# lightino.net
KiCad netlist of a schematic drawn in EAGLE
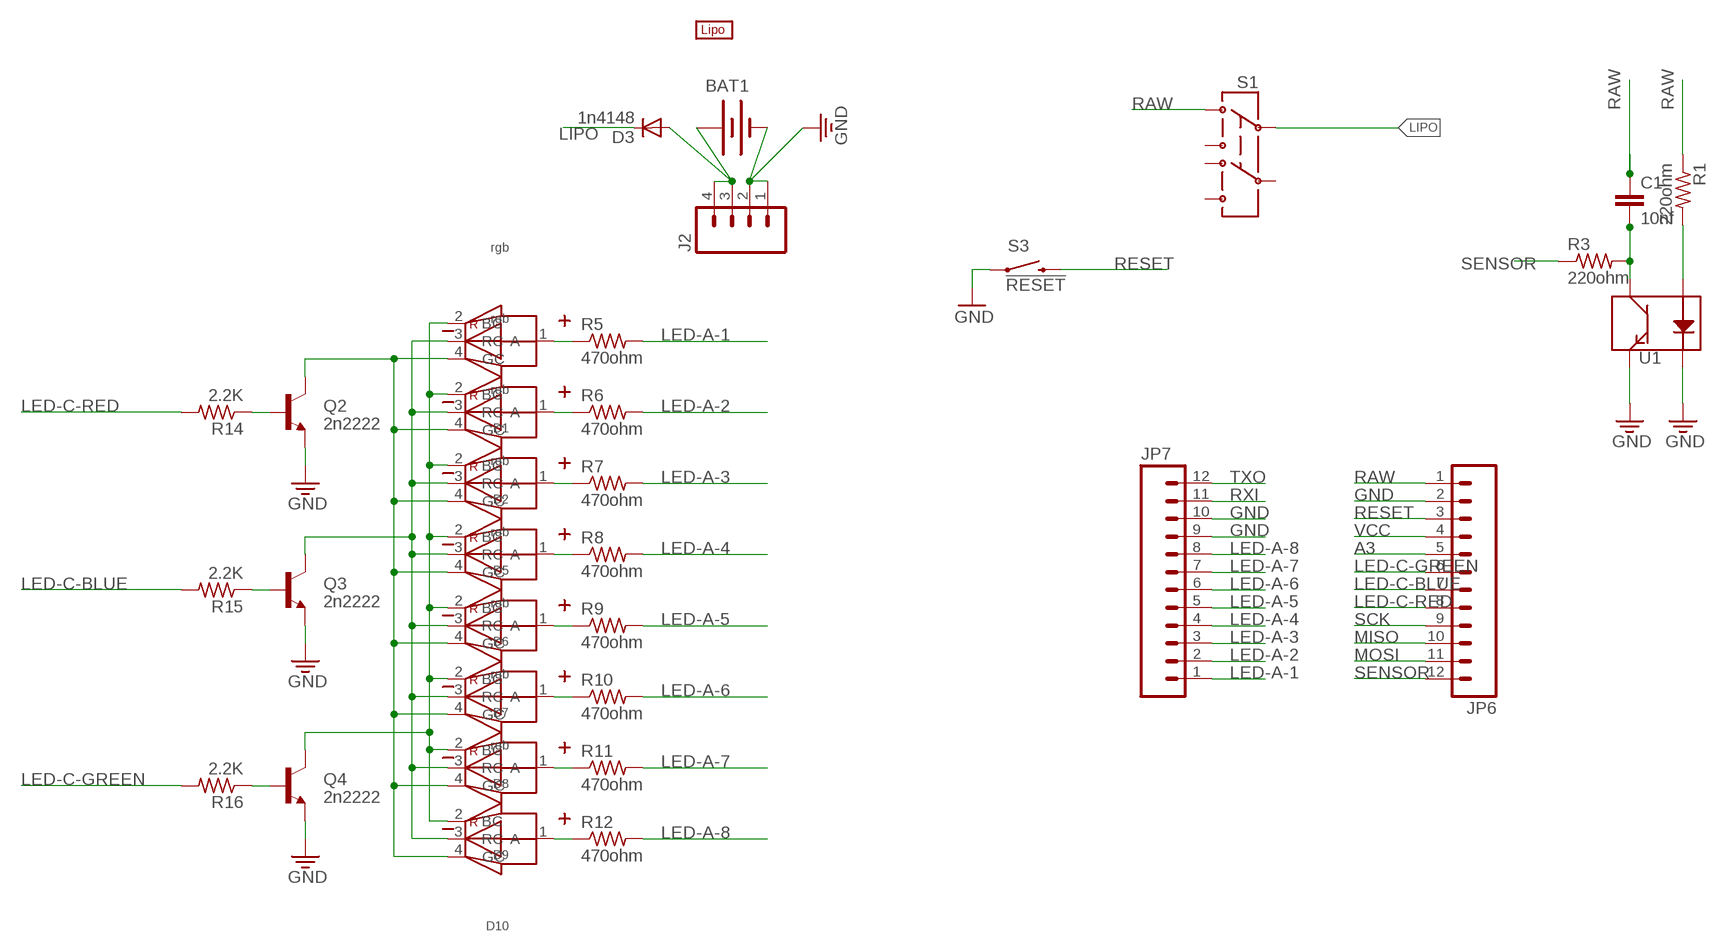
[diagram p0: schematic, sheet 1]

(export (version "E")
  (design (tool "Eeschema 10.0.6"))
  (components
    (comp (ref "BAT1")
      (value "BATTERYLIPO-TABS")
      (footprint "eagle-import:LIPO-110-TABS")
      (libsource (lib "eagle-import") (part "BATTERYLIPO-TABS"))
    )
    (comp (ref "C1")
      (value "10nf")
      (footprint "eagle-import:0805")
      (libsource (lib "eagle-import") (part "CAP0805"))
    )
    (comp (ref "D1")
      (value "rgb")
      (footprint "eagle-import:3528-COMMON-ANODE")
      (libsource (lib "eagle-import") (part "WL-SFTW-150141M173100-R&G&B"))
    )
    (comp (ref "D2")
      (value "rgb")
      (footprint "eagle-import:3528-COMMON-ANODE")
      (libsource (lib "eagle-import") (part "WL-SFTW-150141M173100-R&G&B"))
    )
    (comp (ref "D3")
      (value "1n4148")
      (footprint "eagle-import:SOD-323")
      (libsource (lib "eagle-import") (part "DIODESOD"))
    )
    (comp (ref "D5")
      (value "rgb")
      (footprint "eagle-import:3528-COMMON-ANODE")
      (libsource (lib "eagle-import") (part "WL-SFTW-150141M173100-R&G&B"))
    )
    (comp (ref "D6")
      (value "rgb")
      (footprint "eagle-import:3528-COMMON-ANODE")
      (libsource (lib "eagle-import") (part "WL-SFTW-150141M173100-R&G&B"))
    )
    (comp (ref "D7")
      (value "rgb")
      (footprint "eagle-import:3528-COMMON-ANODE")
      (libsource (lib "eagle-import") (part "WL-SFTW-150141M173100-R&G&B"))
    )
    (comp (ref "D8")
      (value "rgb")
      (footprint "eagle-import:3528-COMMON-ANODE")
      (libsource (lib "eagle-import") (part "WL-SFTW-150141M173100-R&G&B"))
    )
    (comp (ref "D9")
      (value "rgb")
      (footprint "eagle-import:3528-COMMON-ANODE")
      (libsource (lib "eagle-import") (part "WL-SFTW-150141M173100-R&G&B"))
    )
    (comp (ref "D10")
      (value "rgb")
      (footprint "eagle-import:3528-COMMON-ANODE")
      (libsource (lib "eagle-import") (part "WL-SFTW-150141M173100-R&G&B"))
    )
    (comp (ref "J2")
      (value "M041.27MM")
      (footprint "eagle-import:1X04-1.27MM")
      (libsource (lib "eagle-import") (part "M041.27MM"))
    )
    (comp (ref "JP6")
      (value "M12PTH")
      (footprint "eagle-import:1X12")
      (libsource (lib "eagle-import") (part "M12PTH"))
    )
    (comp (ref "JP7")
      (value "M12PTH")
      (footprint "eagle-import:1X12")
      (libsource (lib "eagle-import") (part "M12PTH"))
    )
    (comp (ref "Q2")
      (value "2n2222")
      (footprint "eagle-import:SOT23")
      (libsource (lib "eagle-import") (part "TRANSISTOR_NPNSOT23"))
    )
    (comp (ref "Q3")
      (value "2n2222")
      (footprint "eagle-import:SOT23")
      (libsource (lib "eagle-import") (part "TRANSISTOR_NPNSOT23"))
    )
    (comp (ref "Q4")
      (value "2n2222")
      (footprint "eagle-import:SOT23")
      (libsource (lib "eagle-import") (part "TRANSISTOR_NPNSOT23"))
    )
    (comp (ref "R1")
      (value "220ohm")
      (footprint "eagle-import:M0805")
      (libsource (lib "eagle-import") (part "R-US_M0805"))
    )
    (comp (ref "R3")
      (value "220ohm")
      (footprint "eagle-import:M0805")
      (libsource (lib "eagle-import") (part "R-US_M0805"))
    )
    (comp (ref "R5")
      (value "470ohm")
      (footprint "eagle-import:M0805")
      (libsource (lib "eagle-import") (part "R-US_M0805"))
    )
    (comp (ref "R6")
      (value "470ohm")
      (footprint "eagle-import:M0805")
      (libsource (lib "eagle-import") (part "R-US_M0805"))
    )
    (comp (ref "R7")
      (value "470ohm")
      (footprint "eagle-import:M0805")
      (libsource (lib "eagle-import") (part "R-US_M0805"))
    )
    (comp (ref "R8")
      (value "470ohm")
      (footprint "eagle-import:M0805")
      (libsource (lib "eagle-import") (part "R-US_M0805"))
    )
    (comp (ref "R9")
      (value "470ohm")
      (footprint "eagle-import:M0805")
      (libsource (lib "eagle-import") (part "R-US_M0805"))
    )
    (comp (ref "R10")
      (value "470ohm")
      (footprint "eagle-import:M0805")
      (libsource (lib "eagle-import") (part "R-US_M0805"))
    )
    (comp (ref "R11")
      (value "470ohm")
      (footprint "eagle-import:M0805")
      (libsource (lib "eagle-import") (part "R-US_M0805"))
    )
    (comp (ref "R12")
      (value "470ohm")
      (footprint "eagle-import:M0805")
      (libsource (lib "eagle-import") (part "R-US_M0805"))
    )
    (comp (ref "R14")
      (value "2.2K")
      (footprint "eagle-import:M0805")
      (libsource (lib "eagle-import") (part "R-US_M0805"))
    )
    (comp (ref "R15")
      (value "2.2K")
      (footprint "eagle-import:M0805")
      (libsource (lib "eagle-import") (part "R-US_M0805"))
    )
    (comp (ref "R16")
      (value "2.2K")
      (footprint "eagle-import:M0805")
      (libsource (lib "eagle-import") (part "R-US_M0805"))
    )
    (comp (ref "S1")
      (value "SWITCH-DPDTAYZ0202")
      (footprint "eagle-import:AYZ0202")
      (fields (field (name "PROD_ID") "SWCH-08179"))
      (libsource (lib "eagle-import") (part "SWITCH-DPDTAYZ0202"))
    )
    (comp (ref "S3")
      (value "!RESET")
      (footprint "eagle-import:TACTILE_SWITCH_SMD")
      (fields (field (name "PROD_ID") "SWCH-08247"))
      (libsource (lib "eagle-import") (part "SWITCH-MOMENTARY-2SMD"))
    )
    (comp (ref "U$1")
      (value "LIPO-OUTLINE100")
      (footprint "eagle-import:LIPO-100")
      (libsource (lib "eagle-import") (part "LIPO-OUTLINE100"))
    )
    (comp (ref "U1")
      (value "QRE1113SMD-W")
      (footprint "eagle-import:QRE1113-W")
      (libsource (lib "eagle-import") (part "QRE1113SMD-W"))
    )
  )
  (nets
    (net (code "1") (name "/A3") (class "Default")
      (node (ref "JP6") (pin "5") (pinfunction "5_5") (pintype "passive"))
    )
    (net (code "2") (name "/LED-A-1") (class "Default")
      (node (ref "JP7") (pin "1") (pinfunction "1_1") (pintype "passive"))
      (node (ref "R5") (pin "2") (pinfunction "2_2") (pintype "passive"))
    )
    (net (code "3") (name "/LED-A-2") (class "Default")
      (node (ref "JP7") (pin "2") (pinfunction "2_2") (pintype "passive"))
      (node (ref "R6") (pin "2") (pinfunction "2_2") (pintype "passive"))
    )
    (net (code "4") (name "/LED-A-3") (class "Default")
      (node (ref "JP7") (pin "3") (pinfunction "3_3") (pintype "passive"))
      (node (ref "R7") (pin "2") (pinfunction "2_2") (pintype "passive"))
    )
    (net (code "5") (name "/LED-A-4") (class "Default")
      (node (ref "JP7") (pin "4") (pinfunction "4_4") (pintype "passive"))
      (node (ref "R8") (pin "2") (pinfunction "2_2") (pintype "passive"))
    )
    (net (code "6") (name "/LED-A-5") (class "Default")
      (node (ref "JP7") (pin "5") (pinfunction "5_5") (pintype "passive"))
      (node (ref "R9") (pin "2") (pinfunction "2_2") (pintype "passive"))
    )
    (net (code "7") (name "/LED-A-6") (class "Default")
      (node (ref "JP7") (pin "6") (pinfunction "6_6") (pintype "passive"))
      (node (ref "R10") (pin "2") (pinfunction "2_2") (pintype "passive"))
    )
    (net (code "8") (name "/LED-A-7") (class "Default")
      (node (ref "JP7") (pin "7") (pinfunction "7_7") (pintype "passive"))
      (node (ref "R11") (pin "2") (pinfunction "2_2") (pintype "passive"))
    )
    (net (code "9") (name "/LED-A-8") (class "Default")
      (node (ref "JP7") (pin "8") (pinfunction "8_8") (pintype "passive"))
      (node (ref "R12") (pin "2") (pinfunction "2_2") (pintype "passive"))
    )
    (net (code "10") (name "/LED-C-BLUE") (class "Default")
      (node (ref "JP6") (pin "7") (pinfunction "7_7") (pintype "passive"))
      (node (ref "R15") (pin "2") (pinfunction "2_2") (pintype "passive"))
    )
    (net (code "11") (name "/LED-C-GREEN") (class "Default")
      (node (ref "JP6") (pin "6") (pinfunction "6_6") (pintype "passive"))
      (node (ref "R16") (pin "2") (pinfunction "2_2") (pintype "passive"))
    )
    (net (code "12") (name "/LED-C-RED") (class "Default")
      (node (ref "JP6") (pin "8") (pinfunction "8_8") (pintype "passive"))
      (node (ref "R14") (pin "2") (pinfunction "2_2") (pintype "passive"))
    )
    (net (code "13") (name "/MISO") (class "Default")
      (node (ref "JP6") (pin "10") (pinfunction "10_10") (pintype "passive"))
    )
    (net (code "14") (name "/MOSI") (class "Default")
      (node (ref "JP6") (pin "11") (pinfunction "11_11") (pintype "passive"))
    )
    (net (code "15") (name "/RAW") (class "Default")
      (node (ref "C1") (pin "1") (pinfunction "1_1") (pintype "passive"))
      (node (ref "JP6") (pin "1") (pinfunction "1_1") (pintype "passive"))
      (node (ref "R1") (pin "1") (pinfunction "1_1") (pintype "passive"))
      (node (ref "S1") (pin "1") (pinfunction "1_1") (pintype "bidirectional"))
    )
    (net (code "16") (name "/RESET") (class "Default")
      (node (ref "JP6") (pin "3") (pinfunction "3_3") (pintype "passive"))
      (node (ref "S3") (pin "3") (pinfunction "2_3") (pintype "passive"))
    )
    (net (code "17") (name "/RXI") (class "Default")
      (node (ref "JP7") (pin "11") (pinfunction "11_11") (pintype "passive"))
    )
    (net (code "18") (name "/SCK") (class "Default")
      (node (ref "JP6") (pin "9") (pinfunction "9_9") (pintype "passive"))
    )
    (net (code "19") (name "/SENSOR") (class "Default")
      (node (ref "JP6") (pin "12") (pinfunction "12_12") (pintype "passive"))
      (node (ref "R3") (pin "1") (pinfunction "1_1") (pintype "passive"))
    )
    (net (code "20") (name "/TXO") (class "Default")
      (node (ref "JP7") (pin "12") (pinfunction "12_12") (pintype "passive"))
    )
    (net (code "21") (name "/VCC") (class "Default")
      (node (ref "JP6") (pin "4") (pinfunction "4_4") (pintype "passive"))
    )
    (net (code "22") (name "GND") (class "Default")
      (node (ref "BAT1") (pin "-") (pinfunction "-_-") (pintype "power_in"))
      (node (ref "J2") (pin "1") (pinfunction "1_1") (pintype "passive"))
      (node (ref "J2") (pin "2") (pinfunction "2_2") (pintype "passive"))
      (node (ref "JP6") (pin "2") (pinfunction "2_2") (pintype "passive"))
      (node (ref "JP7") (pin "10") (pinfunction "10_10") (pintype "passive"))
      (node (ref "JP7") (pin "9") (pinfunction "9_9") (pintype "passive"))
      (node (ref "Q2") (pin "2") (pinfunction "E_2") (pintype "passive"))
      (node (ref "Q3") (pin "2") (pinfunction "E_2") (pintype "passive"))
      (node (ref "Q4") (pin "2") (pinfunction "E_2") (pintype "passive"))
      (node (ref "S3") (pin "1") (pinfunction "1_1") (pintype "passive"))
      (node (ref "U1") (pin "2") (pinfunction "K_2") (pintype "bidirectional"))
      (node (ref "U1") (pin "4") (pinfunction "E_4") (pintype "bidirectional"))
    )
    (net (code "23") (name "LIPO") (class "Default")
      (node (ref "D3") (pin "1") (pinfunction "C_1") (pintype "passive"))
      (node (ref "S1") (pin "2") (pinfunction "2_2") (pintype "bidirectional"))
    )
    (net (code "24") (name "Net-(D1-A)") (class "Default")
      (node (ref "D1") (pin "1") (pinfunction "A_1") (pintype "bidirectional"))
      (node (ref "R5") (pin "1") (pinfunction "1_1") (pintype "passive"))
    )
    (net (code "25") (name "Net-(D1-BC)") (class "Default")
      (node (ref "D1") (pin "2") (pinfunction "BC_2") (pintype "bidirectional"))
      (node (ref "D10") (pin "2") (pinfunction "BC_2") (pintype "bidirectional"))
      (node (ref "D2") (pin "2") (pinfunction "BC_2") (pintype "bidirectional"))
      (node (ref "D5") (pin "2") (pinfunction "BC_2") (pintype "bidirectional"))
      (node (ref "D6") (pin "2") (pinfunction "BC_2") (pintype "bidirectional"))
      (node (ref "D7") (pin "2") (pinfunction "BC_2") (pintype "bidirectional"))
      (node (ref "D8") (pin "2") (pinfunction "BC_2") (pintype "bidirectional"))
      (node (ref "D9") (pin "2") (pinfunction "BC_2") (pintype "bidirectional"))
      (node (ref "Q4") (pin "3") (pinfunction "C_3") (pintype "passive"))
    )
    (net (code "26") (name "Net-(D1-GC)") (class "Default")
      (node (ref "D1") (pin "4") (pinfunction "GC_4") (pintype "bidirectional"))
      (node (ref "D10") (pin "4") (pinfunction "GC_4") (pintype "bidirectional"))
      (node (ref "D2") (pin "4") (pinfunction "GC_4") (pintype "bidirectional"))
      (node (ref "D5") (pin "4") (pinfunction "GC_4") (pintype "bidirectional"))
      (node (ref "D6") (pin "4") (pinfunction "GC_4") (pintype "bidirectional"))
      (node (ref "D7") (pin "4") (pinfunction "GC_4") (pintype "bidirectional"))
      (node (ref "D8") (pin "4") (pinfunction "GC_4") (pintype "bidirectional"))
      (node (ref "D9") (pin "4") (pinfunction "GC_4") (pintype "bidirectional"))
      (node (ref "Q2") (pin "3") (pinfunction "C_3") (pintype "passive"))
    )
    (net (code "27") (name "Net-(D1-RC)") (class "Default")
      (node (ref "D1") (pin "3") (pinfunction "RC_3") (pintype "bidirectional"))
      (node (ref "D10") (pin "3") (pinfunction "RC_3") (pintype "bidirectional"))
      (node (ref "D2") (pin "3") (pinfunction "RC_3") (pintype "bidirectional"))
      (node (ref "D5") (pin "3") (pinfunction "RC_3") (pintype "bidirectional"))
      (node (ref "D6") (pin "3") (pinfunction "RC_3") (pintype "bidirectional"))
      (node (ref "D7") (pin "3") (pinfunction "RC_3") (pintype "bidirectional"))
      (node (ref "D8") (pin "3") (pinfunction "RC_3") (pintype "bidirectional"))
      (node (ref "D9") (pin "3") (pinfunction "RC_3") (pintype "bidirectional"))
      (node (ref "Q3") (pin "3") (pinfunction "C_3") (pintype "passive"))
    )
    (net (code "28") (name "Net-(D2-A)") (class "Default")
      (node (ref "D2") (pin "1") (pinfunction "A_1") (pintype "bidirectional"))
      (node (ref "R6") (pin "1") (pinfunction "1_1") (pintype "passive"))
    )
    (net (code "29") (name "Net-(D3-A)") (class "Default")
      (node (ref "BAT1") (pin "+") (pinfunction "+_+") (pintype "power_in"))
      (node (ref "D3") (pin "2") (pinfunction "A_2") (pintype "passive"))
      (node (ref "J2") (pin "3") (pinfunction "3_3") (pintype "passive"))
      (node (ref "J2") (pin "4") (pinfunction "4_4") (pintype "passive"))
    )
    (net (code "30") (name "Net-(D5-A)") (class "Default")
      (node (ref "D5") (pin "1") (pinfunction "A_1") (pintype "bidirectional"))
      (node (ref "R7") (pin "1") (pinfunction "1_1") (pintype "passive"))
    )
    (net (code "31") (name "Net-(D6-A)") (class "Default")
      (node (ref "D6") (pin "1") (pinfunction "A_1") (pintype "bidirectional"))
      (node (ref "R8") (pin "1") (pinfunction "1_1") (pintype "passive"))
    )
    (net (code "32") (name "Net-(D7-A)") (class "Default")
      (node (ref "D7") (pin "1") (pinfunction "A_1") (pintype "bidirectional"))
      (node (ref "R9") (pin "1") (pinfunction "1_1") (pintype "passive"))
    )
    (net (code "33") (name "Net-(D8-A)") (class "Default")
      (node (ref "D8") (pin "1") (pinfunction "A_1") (pintype "bidirectional"))
      (node (ref "R10") (pin "1") (pinfunction "1_1") (pintype "passive"))
    )
    (net (code "34") (name "Net-(D9-A)") (class "Default")
      (node (ref "D9") (pin "1") (pinfunction "A_1") (pintype "bidirectional"))
      (node (ref "R11") (pin "1") (pinfunction "1_1") (pintype "passive"))
    )
    (net (code "35") (name "Net-(D10-A)") (class "Default")
      (node (ref "D10") (pin "1") (pinfunction "A_1") (pintype "bidirectional"))
      (node (ref "R12") (pin "1") (pinfunction "1_1") (pintype "passive"))
    )
    (net (code "36") (name "Net-(Q2-B)") (class "Default")
      (node (ref "Q2") (pin "1") (pinfunction "B_1") (pintype "passive"))
      (node (ref "R14") (pin "1") (pinfunction "1_1") (pintype "passive"))
    )
    (net (code "37") (name "Net-(Q3-B)") (class "Default")
      (node (ref "Q3") (pin "1") (pinfunction "B_1") (pintype "passive"))
      (node (ref "R15") (pin "1") (pinfunction "1_1") (pintype "passive"))
    )
    (net (code "38") (name "Net-(Q4-B)") (class "Default")
      (node (ref "Q4") (pin "1") (pinfunction "B_1") (pintype "passive"))
      (node (ref "R16") (pin "1") (pinfunction "1_1") (pintype "passive"))
    )
    (net (code "39") (name "Net-(U1-A)") (class "Default")
      (node (ref "R1") (pin "2") (pinfunction "2_2") (pintype "passive"))
      (node (ref "U1") (pin "1") (pinfunction "A_1") (pintype "bidirectional"))
    )
    (net (code "40") (name "Net-(U1-C)") (class "Default")
      (node (ref "C1") (pin "2") (pinfunction "2_2") (pintype "passive"))
      (node (ref "R3") (pin "2") (pinfunction "2_2") (pintype "passive"))
      (node (ref "U1") (pin "3") (pinfunction "C_3") (pintype "bidirectional"))
    )
    (net (code "41") (name "unconnected-(S1-Pad3)") (class "Default")
      (node (ref "S1") (pin "3") (pinfunction "3_3") (pintype "bidirectional"))
    )
    (net (code "42") (name "unconnected-(S1-Pad4)") (class "Default")
      (node (ref "S1") (pin "4") (pinfunction "4_4") (pintype "bidirectional"))
    )
    (net (code "43") (name "unconnected-(S1-Pad5)") (class "Default")
      (node (ref "S1") (pin "5") (pinfunction "5_5") (pintype "bidirectional"))
    )
    (net (code "44") (name "unconnected-(S1-Pad6)") (class "Default")
      (node (ref "S1") (pin "6") (pinfunction "6_6") (pintype "bidirectional"))
    )
  )
)
